# CFA_T.net
KiCad netlist of a schematic drawn in EAGLE
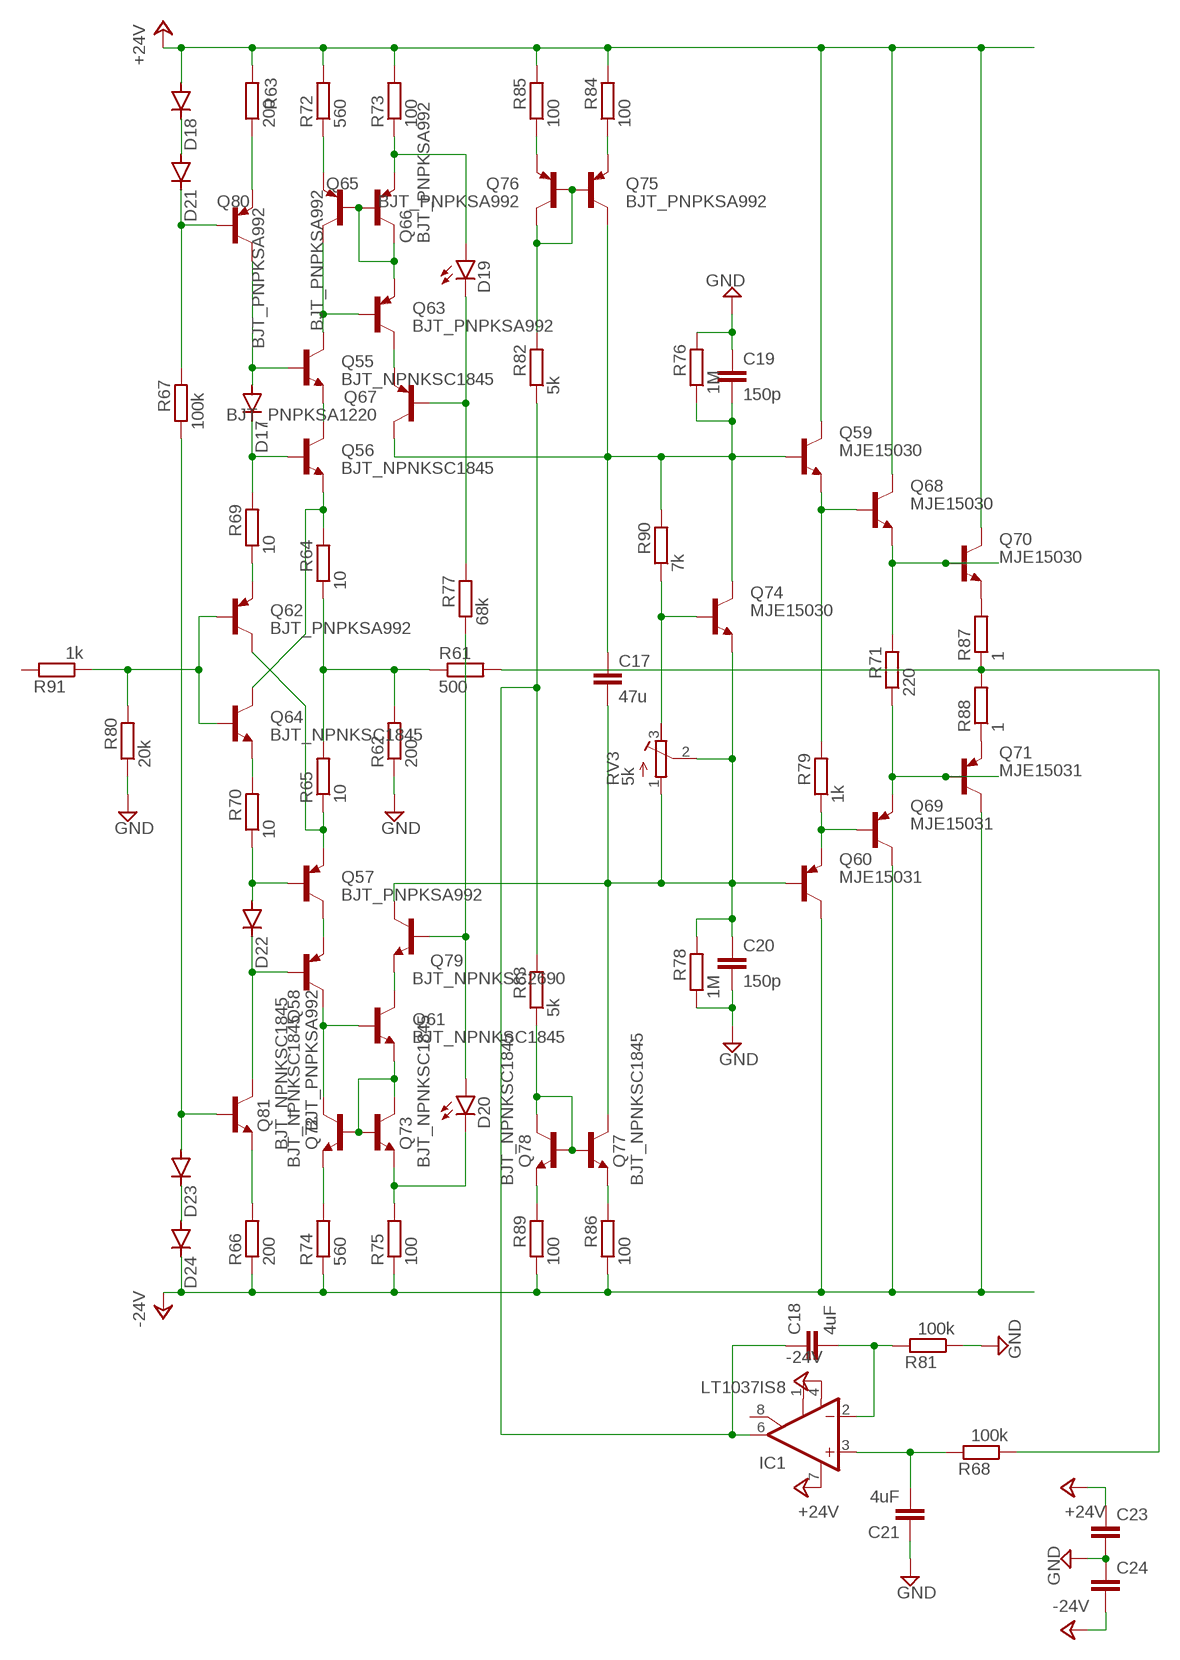
[diagram p0: schematic, sheet 1]

(export (version "E")
  (design (tool "Eeschema 10.0.6"))
  (components
    (comp (ref "C17")
      (value "47u")
      (footprint "eagle-import:C1210")
      (fields (field (name "SPICEPREFIX") "C"))
      (libsource (lib "eagle-import") (part "C-EUC1210"))
    )
    (comp (ref "C18")
      (value "4uF")
      (footprint "eagle-import:C1210")
      (fields (field (name "SPICEPREFIX") "C"))
      (libsource (lib "eagle-import") (part "C-EUC1210"))
    )
    (comp (ref "C19")
      (value "150p")
      (footprint "eagle-import:C0805")
      (fields (field (name "SPICEPREFIX") "C"))
      (libsource (lib "eagle-import") (part "C-EUC0805"))
    )
    (comp (ref "C20")
      (value "150p")
      (footprint "eagle-import:C0805")
      (fields (field (name "SPICEPREFIX") "C"))
      (libsource (lib "eagle-import") (part "C-EUC0805"))
    )
    (comp (ref "C21")
      (value "4uF")
      (footprint "eagle-import:C1210")
      (fields (field (name "SPICEPREFIX") "C"))
      (libsource (lib "eagle-import") (part "C-EUC1210"))
    )
    (comp (ref "C23")
      (value "C-EUC0603K")
      (footprint "eagle-import:C0603K")
      (libsource (lib "eagle-import") (part "C-EUC0603K"))
    )
    (comp (ref "C24")
      (value "C-EUC0603K")
      (footprint "eagle-import:C0603K")
      (libsource (lib "eagle-import") (part "C-EUC0603K"))
    )
    (comp (ref "D17")
      (value "DIODE-SOD80C")
      (footprint "eagle-import:SOD80C")
      (fields (field (name "SPICEPREFIX") "D"))
      (libsource (lib "eagle-import") (part "DIODE-SOD80C"))
    )
    (comp (ref "D18")
      (value "DIODE-SOD80C")
      (footprint "eagle-import:SOD80C")
      (fields (field (name "SPICEPREFIX") "D"))
      (libsource (lib "eagle-import") (part "DIODE-SOD80C"))
    )
    (comp (ref "D19")
      (value "LEDCHIPLED_1206")
      (footprint "eagle-import:CHIPLED_1206")
      (fields (field (name "SPICEPREFIX") "D"))
      (libsource (lib "eagle-import") (part "LEDCHIPLED_1206"))
    )
    (comp (ref "D20")
      (value "LEDCHIPLED_1206")
      (footprint "eagle-import:CHIPLED_1206")
      (fields (field (name "SPICEPREFIX") "D"))
      (libsource (lib "eagle-import") (part "LEDCHIPLED_1206"))
    )
    (comp (ref "D21")
      (value "DIODE-SOD80C")
      (footprint "eagle-import:SOD80C")
      (fields (field (name "SPICEPREFIX") "D"))
      (libsource (lib "eagle-import") (part "DIODE-SOD80C"))
    )
    (comp (ref "D22")
      (value "DIODE-SOD80C")
      (footprint "eagle-import:SOD80C")
      (fields (field (name "SPICEPREFIX") "D"))
      (libsource (lib "eagle-import") (part "DIODE-SOD80C"))
    )
    (comp (ref "D23")
      (value "DIODE-SOD80C")
      (footprint "eagle-import:SOD80C")
      (fields (field (name "SPICEPREFIX") "D"))
      (libsource (lib "eagle-import") (part "DIODE-SOD80C"))
    )
    (comp (ref "D24")
      (value "DIODE-SOD80C")
      (footprint "eagle-import:SOD80C")
      (fields (field (name "SPICEPREFIX") "D"))
      (libsource (lib "eagle-import") (part "DIODE-SOD80C"))
    )
    (comp (ref "IC1")
      (value "LT1037IS8")
      (footprint "eagle-import:SOIC8")
      (libsource (lib "eagle-import") (part "LT10S837I"))
    )
    (comp (ref "Q55")
      (value "BJT_NPNKSC1845")
      (footprint "eagle-import:TRANSISTOR_TO92-ECB")
      (fields (field (name "SPICEPREFIX") "Q"))
      (libsource (lib "eagle-import") (part "BJT_NPNKSC1845"))
    )
    (comp (ref "Q56")
      (value "BJT_NPNKSC1845")
      (footprint "eagle-import:TRANSISTOR_TO92-ECB")
      (fields (field (name "SPICEPREFIX") "Q"))
      (libsource (lib "eagle-import") (part "BJT_NPNKSC1845"))
    )
    (comp (ref "Q57")
      (value "BJT_PNPKSA992")
      (footprint "eagle-import:TRANSISTOR_TO92-ECB")
      (fields (field (name "SPICEPREFIX") "Q"))
      (libsource (lib "eagle-import") (part "BJT_PNPKSA992"))
    )
    (comp (ref "Q58")
      (value "BJT_PNPKSA992")
      (footprint "eagle-import:TRANSISTOR_TO92-ECB")
      (fields (field (name "SPICEPREFIX") "Q"))
      (libsource (lib "eagle-import") (part "BJT_PNPKSA992"))
    )
    (comp (ref "Q59")
      (value "MJE15030")
      (footprint "eagle-import:TRANSISTOR_TO92-ECB")
      (fields (field (name "SPICEPREFIX") "Q"))
      (libsource (lib "eagle-import") (part "BJT_NPNKSC1845"))
    )
    (comp (ref "Q60")
      (value "MJE15031")
      (footprint "eagle-import:TRANSISTOR_TO92-ECB")
      (fields (field (name "SPICEPREFIX") "Q"))
      (libsource (lib "eagle-import") (part "BJT_PNPKSA992"))
    )
    (comp (ref "Q61")
      (value "BJT_NPNKSC1845")
      (footprint "eagle-import:TRANSISTOR_TO92-ECB")
      (fields (field (name "SPICEPREFIX") "Q"))
      (libsource (lib "eagle-import") (part "BJT_NPNKSC1845"))
    )
    (comp (ref "Q62")
      (value "BJT_PNPKSA992")
      (footprint "eagle-import:TRANSISTOR_TO92-ECB")
      (fields (field (name "SPICEPREFIX") "Q"))
      (libsource (lib "eagle-import") (part "BJT_PNPKSA992"))
    )
    (comp (ref "Q63")
      (value "BJT_PNPKSA992")
      (footprint "eagle-import:TRANSISTOR_TO92-ECB")
      (fields (field (name "SPICEPREFIX") "Q"))
      (libsource (lib "eagle-import") (part "BJT_PNPKSA992"))
    )
    (comp (ref "Q64")
      (value "BJT_NPNKSC1845")
      (footprint "eagle-import:TRANSISTOR_TO92-ECB")
      (fields (field (name "SPICEPREFIX") "Q"))
      (libsource (lib "eagle-import") (part "BJT_NPNKSC1845"))
    )
    (comp (ref "Q65")
      (value "BJT_PNPKSA992")
      (footprint "eagle-import:TRANSISTOR_TO92-ECB")
      (fields (field (name "SPICEPREFIX") "Q"))
      (libsource (lib "eagle-import") (part "BJT_PNPKSA992"))
    )
    (comp (ref "Q66")
      (value "BJT_PNPKSA992")
      (footprint "eagle-import:TRANSISTOR_TO92-ECB")
      (fields (field (name "SPICEPREFIX") "Q"))
      (libsource (lib "eagle-import") (part "BJT_PNPKSA992"))
    )
    (comp (ref "Q67")
      (value "BJT_PNPKSA1220")
      (footprint "eagle-import:TRANSISTOR_TO126V")
      (fields (field (name "SPICEPREFIX") "Q"))
      (libsource (lib "eagle-import") (part "BJT_PNPKSA1220"))
    )
    (comp (ref "Q68")
      (value "MJE15030")
      (footprint "eagle-import:TRANSISTOR_TO92-ECB")
      (fields (field (name "SPICEPREFIX") "Q"))
      (libsource (lib "eagle-import") (part "BJT_NPNKSC1845"))
    )
    (comp (ref "Q69")
      (value "MJE15031")
      (footprint "eagle-import:TRANSISTOR_TO92-ECB")
      (fields (field (name "SPICEPREFIX") "Q"))
      (libsource (lib "eagle-import") (part "BJT_PNPKSA992"))
    )
    (comp (ref "Q70")
      (value "MJE15030")
      (footprint "eagle-import:TO264_TO-264")
      (fields (field (name "SPICEPREFIX") "Q"))
      (libsource (lib "eagle-import") (part "TO264_MJL4281"))
    )
    (comp (ref "Q71")
      (value "MJE15031")
      (footprint "eagle-import:TO264_TO-264")
      (fields (field (name "SPICEPREFIX") "Q"))
      (libsource (lib "eagle-import") (part "TO264_MJL4302"))
    )
    (comp (ref "Q72")
      (value "BJT_NPNKSC1845")
      (footprint "eagle-import:TRANSISTOR_TO92-ECB")
      (fields (field (name "SPICEPREFIX") "Q"))
      (libsource (lib "eagle-import") (part "BJT_NPNKSC1845"))
    )
    (comp (ref "Q73")
      (value "BJT_NPNKSC1845")
      (footprint "eagle-import:TRANSISTOR_TO92-ECB")
      (fields (field (name "SPICEPREFIX") "Q"))
      (libsource (lib "eagle-import") (part "BJT_NPNKSC1845"))
    )
    (comp (ref "Q74")
      (value "MJE15030")
      (footprint "eagle-import:TRANSISTOR_TO220KG")
      (fields (field (name "SPICEPREFIX") "Q"))
      (libsource (lib "eagle-import") (part "TRANSISTOR_MJE15030"))
    )
    (comp (ref "Q75")
      (value "BJT_PNPKSA992")
      (footprint "eagle-import:TRANSISTOR_TO92-ECB")
      (fields (field (name "SPICEPREFIX") "Q"))
      (libsource (lib "eagle-import") (part "BJT_PNPKSA992"))
    )
    (comp (ref "Q76")
      (value "BJT_PNPKSA992")
      (footprint "eagle-import:TRANSISTOR_TO92-ECB")
      (fields (field (name "SPICEPREFIX") "Q"))
      (libsource (lib "eagle-import") (part "BJT_PNPKSA992"))
    )
    (comp (ref "Q77")
      (value "BJT_NPNKSC1845")
      (footprint "eagle-import:TRANSISTOR_TO92-ECB")
      (fields (field (name "SPICEPREFIX") "Q"))
      (libsource (lib "eagle-import") (part "BJT_NPNKSC1845"))
    )
    (comp (ref "Q78")
      (value "BJT_NPNKSC1845")
      (footprint "eagle-import:TRANSISTOR_TO92-ECB")
      (fields (field (name "SPICEPREFIX") "Q"))
      (libsource (lib "eagle-import") (part "BJT_NPNKSC1845"))
    )
    (comp (ref "Q79")
      (value "BJT_NPNKSC2690")
      (footprint "eagle-import:TRANSISTOR_TO126V")
      (fields (field (name "SPICEPREFIX") "Q"))
      (libsource (lib "eagle-import") (part "BJT_NPNKSC2690"))
    )
    (comp (ref "Q80")
      (value "BJT_PNPKSA992")
      (footprint "eagle-import:TRANSISTOR_TO92-ECB")
      (fields (field (name "SPICEPREFIX") "Q"))
      (libsource (lib "eagle-import") (part "BJT_PNPKSA992"))
    )
    (comp (ref "Q81")
      (value "BJT_NPNKSC1845")
      (footprint "eagle-import:TRANSISTOR_TO92-ECB")
      (fields (field (name "SPICEPREFIX") "Q"))
      (libsource (lib "eagle-import") (part "BJT_NPNKSC1845"))
    )
    (comp (ref "R61")
      (value "500")
      (footprint "eagle-import:MINI_MELF-0204W")
      (fields (field (name "SPICEPREFIX") "R"))
      (libsource (lib "eagle-import") (part "R-EU_MELF0204W"))
    )
    (comp (ref "R62")
      (value "200")
      (footprint "eagle-import:MINI_MELF-0204W")
      (fields (field (name "SPICEPREFIX") "R"))
      (libsource (lib "eagle-import") (part "R-EU_MELF0204W"))
    )
    (comp (ref "R63")
      (value "200")
      (footprint "eagle-import:MINI_MELF-0204W")
      (fields (field (name "SPICEPREFIX") "R"))
      (libsource (lib "eagle-import") (part "R-EU_MELF0204W"))
    )
    (comp (ref "R64")
      (value "10")
      (footprint "eagle-import:MINI_MELF-0204W")
      (fields (field (name "SPICEPREFIX") "R"))
      (libsource (lib "eagle-import") (part "R-EU_MELF0204W"))
    )
    (comp (ref "R65")
      (value "10")
      (footprint "eagle-import:MINI_MELF-0204W")
      (fields (field (name "SPICEPREFIX") "R"))
      (libsource (lib "eagle-import") (part "R-EU_MELF0204W"))
    )
    (comp (ref "R66")
      (value "200")
      (footprint "eagle-import:MINI_MELF-0204W")
      (fields (field (name "SPICEPREFIX") "R"))
      (libsource (lib "eagle-import") (part "R-EU_MELF0204W"))
    )
    (comp (ref "R67")
      (value "100k")
      (footprint "eagle-import:MINI_MELF-0204W")
      (fields (field (name "SPICEPREFIX") "R"))
      (libsource (lib "eagle-import") (part "R-EU_MELF0204W"))
    )
    (comp (ref "R68")
      (value "100k")
      (footprint "eagle-import:MINI_MELF-0204W")
      (fields (field (name "SPICEPREFIX") "R"))
      (libsource (lib "eagle-import") (part "R-EU_MELF0204W"))
    )
    (comp (ref "R69")
      (value "10")
      (footprint "eagle-import:MINI_MELF-0204W")
      (fields (field (name "SPICEPREFIX") "R"))
      (libsource (lib "eagle-import") (part "R-EU_MELF0204W"))
    )
    (comp (ref "R70")
      (value "10")
      (footprint "eagle-import:MINI_MELF-0204W")
      (fields (field (name "SPICEPREFIX") "R"))
      (libsource (lib "eagle-import") (part "R-EU_MELF0204W"))
    )
    (comp (ref "R71")
      (value "220")
      (footprint "eagle-import:MINI_MELF-0204W")
      (fields (field (name "SPICEPREFIX") "R"))
      (libsource (lib "eagle-import") (part "R-EU_MELF0204W"))
    )
    (comp (ref "R72")
      (value "560")
      (footprint "eagle-import:MINI_MELF-0204W")
      (fields (field (name "SPICEPREFIX") "R"))
      (libsource (lib "eagle-import") (part "R-EU_MELF0204W"))
    )
    (comp (ref "R73")
      (value "100")
      (footprint "eagle-import:MINI_MELF-0204W")
      (fields (field (name "SPICEPREFIX") "R"))
      (libsource (lib "eagle-import") (part "R-EU_MELF0204W"))
    )
    (comp (ref "R74")
      (value "560")
      (footprint "eagle-import:MINI_MELF-0204W")
      (fields (field (name "SPICEPREFIX") "R"))
      (libsource (lib "eagle-import") (part "R-EU_MELF0204W"))
    )
    (comp (ref "R75")
      (value "100")
      (footprint "eagle-import:MINI_MELF-0204W")
      (fields (field (name "SPICEPREFIX") "R"))
      (libsource (lib "eagle-import") (part "R-EU_MELF0204W"))
    )
    (comp (ref "R76")
      (value "1M")
      (footprint "eagle-import:MINI_MELF-0204W")
      (fields (field (name "SPICEPREFIX") "R"))
      (libsource (lib "eagle-import") (part "R-EU_MELF0204W"))
    )
    (comp (ref "R77")
      (value "68k")
      (footprint "eagle-import:MINI_MELF-0204W")
      (fields (field (name "SPICEPREFIX") "R"))
      (libsource (lib "eagle-import") (part "R-EU_MELF0204W"))
    )
    (comp (ref "R78")
      (value "1M")
      (footprint "eagle-import:MINI_MELF-0204W")
      (fields (field (name "SPICEPREFIX") "R"))
      (libsource (lib "eagle-import") (part "R-EU_MELF0204W"))
    )
    (comp (ref "R79")
      (value "1k")
      (footprint "eagle-import:MINI_MELF-0204W")
      (fields (field (name "SPICEPREFIX") "R"))
      (libsource (lib "eagle-import") (part "R-EU_MELF0204W"))
    )
    (comp (ref "R80")
      (value "20k")
      (footprint "eagle-import:MINI_MELF-0204W")
      (fields (field (name "SPICEPREFIX") "R"))
      (libsource (lib "eagle-import") (part "R-EU_MELF0204W"))
    )
    (comp (ref "R81")
      (value "100k")
      (footprint "eagle-import:MINI_MELF-0204W")
      (fields (field (name "SPICEPREFIX") "R"))
      (libsource (lib "eagle-import") (part "R-EU_MELF0204W"))
    )
    (comp (ref "R82")
      (value "5k")
      (footprint "eagle-import:MINI_MELF-0204W")
      (fields (field (name "SPICEPREFIX") "R"))
      (libsource (lib "eagle-import") (part "R-EU_MELF0204W"))
    )
    (comp (ref "R83")
      (value "5k")
      (footprint "eagle-import:MINI_MELF-0204W")
      (fields (field (name "SPICEPREFIX") "R"))
      (libsource (lib "eagle-import") (part "R-EU_MELF0204W"))
    )
    (comp (ref "R84")
      (value "100")
      (footprint "eagle-import:MINI_MELF-0204W")
      (fields (field (name "SPICEPREFIX") "R"))
      (libsource (lib "eagle-import") (part "R-EU_MELF0204W"))
    )
    (comp (ref "R85")
      (value "100")
      (footprint "eagle-import:MINI_MELF-0204W")
      (fields (field (name "SPICEPREFIX") "R"))
      (libsource (lib "eagle-import") (part "R-EU_MELF0204W"))
    )
    (comp (ref "R86")
      (value "100")
      (footprint "eagle-import:MINI_MELF-0204W")
      (fields (field (name "SPICEPREFIX") "R"))
      (libsource (lib "eagle-import") (part "R-EU_MELF0204W"))
    )
    (comp (ref "R87")
      (value "1")
      (footprint "eagle-import:R2512")
      (fields (field (name "SPICEPREFIX") "R"))
      (libsource (lib "eagle-import") (part "R-EU_R2512"))
    )
    (comp (ref "R88")
      (value "1")
      (footprint "eagle-import:R2512")
      (fields (field (name "SPICEPREFIX") "R"))
      (libsource (lib "eagle-import") (part "R-EU_R2512"))
    )
    (comp (ref "R89")
      (value "100")
      (footprint "eagle-import:MINI_MELF-0204W")
      (fields (field (name "SPICEPREFIX") "R"))
      (libsource (lib "eagle-import") (part "R-EU_MELF0204W"))
    )
    (comp (ref "R90")
      (value "7k")
      (footprint "eagle-import:MINI_MELF-0204W")
      (fields (field (name "SPICEPREFIX") "R"))
      (libsource (lib "eagle-import") (part "R-EU_MELF0204W"))
    )
    (comp (ref "R91")
      (value "1k")
      (footprint "eagle-import:MINI_MELF-0204W")
      (fields (field (name "SPICEPREFIX") "R"))
      (libsource (lib "eagle-import") (part "R-EU_MELF0204W"))
    )
    (comp (ref "RV3")
      (value "5k")
      (footprint "eagle-import:RTRIM3296W")
      (fields (field (name "SPICEPREFIX") "Z"))
      (libsource (lib "eagle-import") (part "R-TRIMM3296W"))
    )
  )
  (nets
    (net (code "1") (name "+24V") (class "Default")
      (node (ref "C23") (pin "1") (pinfunction "1_1") (pintype "passive"))
      (node (ref "D18") (pin "A") (pinfunction "A_A") (pintype "passive"))
      (node (ref "IC1") (pin "7") (pinfunction "V+_7") (pintype "power_in"))
      (node (ref "Q59") (pin "C") (pinfunction "C_C") (pintype "passive"))
      (node (ref "Q68") (pin "C") (pinfunction "C_C") (pintype "passive"))
      (node (ref "Q70") (pin "C") (pinfunction "C_C") (pintype "passive"))
      (node (ref "R63") (pin "2") (pinfunction "2_2") (pintype "passive"))
      (node (ref "R72") (pin "2") (pinfunction "2_2") (pintype "passive"))
      (node (ref "R73") (pin "2") (pinfunction "2_2") (pintype "passive"))
      (node (ref "R84") (pin "2") (pinfunction "2_2") (pintype "passive"))
      (node (ref "R85") (pin "2") (pinfunction "2_2") (pintype "passive"))
    )
    (net (code "2") (name "-24V") (class "Default")
      (node (ref "C24") (pin "2") (pinfunction "2_2") (pintype "passive"))
      (node (ref "D24") (pin "C") (pinfunction "C_C") (pintype "passive"))
      (node (ref "IC1") (pin "4") (pinfunction "V-_4") (pintype "power_in"))
      (node (ref "Q60") (pin "C") (pinfunction "C_C") (pintype "passive"))
      (node (ref "Q69") (pin "C") (pinfunction "C_C") (pintype "passive"))
      (node (ref "Q71") (pin "C") (pinfunction "C_C") (pintype "passive"))
      (node (ref "R66") (pin "1") (pinfunction "1_1") (pintype "passive"))
      (node (ref "R74") (pin "1") (pinfunction "1_1") (pintype "passive"))
      (node (ref "R75") (pin "1") (pinfunction "1_1") (pintype "passive"))
      (node (ref "R86") (pin "1") (pinfunction "1_1") (pintype "passive"))
      (node (ref "R89") (pin "1") (pinfunction "1_1") (pintype "passive"))
    )
    (net (code "3") (name "GND") (class "Default")
      (node (ref "C19") (pin "1") (pinfunction "1_1") (pintype "passive"))
      (node (ref "C20") (pin "2") (pinfunction "2_2") (pintype "passive"))
      (node (ref "C21") (pin "1") (pinfunction "1_1") (pintype "passive"))
      (node (ref "C23") (pin "2") (pinfunction "2_2") (pintype "passive"))
      (node (ref "C24") (pin "1") (pinfunction "1_1") (pintype "passive"))
      (node (ref "R62") (pin "1") (pinfunction "1_1") (pintype "passive"))
      (node (ref "R76") (pin "2") (pinfunction "2_2") (pintype "passive"))
      (node (ref "R78") (pin "1") (pinfunction "1_1") (pintype "passive"))
      (node (ref "R80") (pin "1") (pinfunction "1_1") (pintype "passive"))
      (node (ref "R81") (pin "1") (pinfunction "1_1") (pintype "passive"))
    )
    (net (code "4") (name "Net-(D17-PadA)") (class "Default")
      (node (ref "D17") (pin "A") (pinfunction "A_A") (pintype "passive"))
      (node (ref "Q55") (pin "B") (pinfunction "B_B") (pintype "passive"))
      (node (ref "Q80") (pin "C") (pinfunction "C_C") (pintype "passive"))
    )
    (net (code "5") (name "Net-(D17-PadC)") (class "Default")
      (node (ref "D17") (pin "C") (pinfunction "C_C") (pintype "passive"))
      (node (ref "Q56") (pin "B") (pinfunction "B_B") (pintype "passive"))
      (node (ref "R69") (pin "2") (pinfunction "2_2") (pintype "passive"))
    )
    (net (code "6") (name "Net-(D18-PadC)") (class "Default")
      (node (ref "D18") (pin "C") (pinfunction "C_C") (pintype "passive"))
      (node (ref "D21") (pin "A") (pinfunction "A_A") (pintype "passive"))
    )
    (net (code "7") (name "Net-(D19-PadA)") (class "Default")
      (node (ref "D19") (pin "A") (pinfunction "A_A") (pintype "passive"))
      (node (ref "Q66") (pin "E") (pinfunction "E_E") (pintype "passive"))
      (node (ref "R73") (pin "1") (pinfunction "1_1") (pintype "passive"))
    )
    (net (code "8") (name "Net-(D19-PadC)") (class "Default")
      (node (ref "D19") (pin "C") (pinfunction "C_C") (pintype "passive"))
      (node (ref "Q67") (pin "B") (pinfunction "B_B") (pintype "passive"))
      (node (ref "R77") (pin "2") (pinfunction "2_2") (pintype "passive"))
    )
    (net (code "9") (name "Net-(D20-PadA)") (class "Default")
      (node (ref "D20") (pin "A") (pinfunction "A_A") (pintype "passive"))
      (node (ref "Q79") (pin "B") (pinfunction "B_B") (pintype "passive"))
      (node (ref "R77") (pin "1") (pinfunction "1_1") (pintype "passive"))
    )
    (net (code "10") (name "Net-(D20-PadC)") (class "Default")
      (node (ref "D20") (pin "C") (pinfunction "C_C") (pintype "passive"))
      (node (ref "Q73") (pin "E") (pinfunction "E_E") (pintype "passive"))
      (node (ref "R75") (pin "2") (pinfunction "2_2") (pintype "passive"))
    )
    (net (code "11") (name "Net-(D21-PadC)") (class "Default")
      (node (ref "D21") (pin "C") (pinfunction "C_C") (pintype "passive"))
      (node (ref "Q80") (pin "B") (pinfunction "B_B") (pintype "passive"))
      (node (ref "R67") (pin "2") (pinfunction "2_2") (pintype "passive"))
    )
    (net (code "12") (name "Net-(D22-PadA)") (class "Default")
      (node (ref "D22") (pin "A") (pinfunction "A_A") (pintype "passive"))
      (node (ref "Q57") (pin "B") (pinfunction "B_B") (pintype "passive"))
      (node (ref "R70") (pin "1") (pinfunction "1_1") (pintype "passive"))
    )
    (net (code "13") (name "Net-(D22-PadC)") (class "Default")
      (node (ref "D22") (pin "C") (pinfunction "C_C") (pintype "passive"))
      (node (ref "Q58") (pin "B") (pinfunction "B_B") (pintype "passive"))
      (node (ref "Q81") (pin "C") (pinfunction "C_C") (pintype "passive"))
    )
    (net (code "14") (name "Net-(D23-PadA)") (class "Default")
      (node (ref "D23") (pin "A") (pinfunction "A_A") (pintype "passive"))
      (node (ref "Q81") (pin "B") (pinfunction "B_B") (pintype "passive"))
      (node (ref "R67") (pin "1") (pinfunction "1_1") (pintype "passive"))
    )
    (net (code "15") (name "Net-(D23-PadC)") (class "Default")
      (node (ref "D23") (pin "C") (pinfunction "C_C") (pintype "passive"))
      (node (ref "D24") (pin "A") (pinfunction "A_A") (pintype "passive"))
    )
    (net (code "16") (name "Net-(IC1-+IN)") (class "Default")
      (node (ref "C21") (pin "2") (pinfunction "2_2") (pintype "passive"))
      (node (ref "IC1") (pin "3") (pinfunction "+IN_3") (pintype "input"))
      (node (ref "R68") (pin "2") (pinfunction "2_2") (pintype "passive"))
    )
    (net (code "17") (name "Net-(IC1--IN)") (class "Default")
      (node (ref "C18") (pin "2") (pinfunction "2_2") (pintype "passive"))
      (node (ref "IC1") (pin "2") (pinfunction "-IN_2") (pintype "input"))
      (node (ref "R81") (pin "2") (pinfunction "2_2") (pintype "passive"))
    )
    (net (code "18") (name "Net-(IC1-OUT)") (class "Default")
      (node (ref "C18") (pin "1") (pinfunction "1_1") (pintype "passive"))
      (node (ref "IC1") (pin "6") (pinfunction "OUT_6") (pintype "output"))
      (node (ref "R82") (pin "1") (pinfunction "1_1") (pintype "passive"))
      (node (ref "R83") (pin "2") (pinfunction "2_2") (pintype "passive"))
    )
    (net (code "19") (name "Net-(Q55-PadC)") (class "Default")
      (node (ref "Q55") (pin "C") (pinfunction "C_C") (pintype "passive"))
      (node (ref "Q63") (pin "B") (pinfunction "B_B") (pintype "passive"))
      (node (ref "Q65") (pin "C") (pinfunction "C_C") (pintype "passive"))
    )
    (net (code "20") (name "Net-(Q55-PadE)") (class "Default")
      (node (ref "Q55") (pin "E") (pinfunction "E_E") (pintype "passive"))
      (node (ref "Q56") (pin "C") (pinfunction "C_C") (pintype "passive"))
    )
    (net (code "21") (name "Net-(Q56-PadE)") (class "Default")
      (node (ref "Q56") (pin "E") (pinfunction "E_E") (pintype "passive"))
      (node (ref "Q64") (pin "C") (pinfunction "C_C") (pintype "passive"))
      (node (ref "R64") (pin "2") (pinfunction "2_2") (pintype "passive"))
    )
    (net (code "22") (name "Net-(Q57-PadC)") (class "Default")
      (node (ref "Q57") (pin "C") (pinfunction "C_C") (pintype "passive"))
      (node (ref "Q58") (pin "E") (pinfunction "E_E") (pintype "passive"))
    )
    (net (code "23") (name "Net-(Q57-PadE)") (class "Default")
      (node (ref "Q57") (pin "E") (pinfunction "E_E") (pintype "passive"))
      (node (ref "Q62") (pin "C") (pinfunction "C_C") (pintype "passive"))
      (node (ref "R65") (pin "1") (pinfunction "1_1") (pintype "passive"))
    )
    (net (code "24") (name "Net-(Q58-PadC)") (class "Default")
      (node (ref "Q58") (pin "C") (pinfunction "C_C") (pintype "passive"))
      (node (ref "Q61") (pin "B") (pinfunction "B_B") (pintype "passive"))
      (node (ref "Q72") (pin "C") (pinfunction "C_C") (pintype "passive"))
    )
    (net (code "25") (name "Net-(Q59-PadE)") (class "Default")
      (node (ref "Q59") (pin "E") (pinfunction "E_E") (pintype "passive"))
      (node (ref "Q68") (pin "B") (pinfunction "B_B") (pintype "passive"))
      (node (ref "R79") (pin "2") (pinfunction "2_2") (pintype "passive"))
    )
    (net (code "26") (name "Net-(Q60-PadE)") (class "Default")
      (node (ref "Q60") (pin "E") (pinfunction "E_E") (pintype "passive"))
      (node (ref "Q69") (pin "B") (pinfunction "B_B") (pintype "passive"))
      (node (ref "R79") (pin "1") (pinfunction "1_1") (pintype "passive"))
    )
    (net (code "27") (name "Net-(Q61-PadC)") (class "Default")
      (node (ref "Q61") (pin "C") (pinfunction "C_C") (pintype "passive"))
      (node (ref "Q79") (pin "E") (pinfunction "E_E") (pintype "passive"))
    )
    (net (code "28") (name "Net-(Q61-PadE)") (class "Default")
      (node (ref "Q61") (pin "E") (pinfunction "E_E") (pintype "passive"))
      (node (ref "Q72") (pin "B") (pinfunction "B_B") (pintype "passive"))
      (node (ref "Q73") (pin "B") (pinfunction "B_B") (pintype "passive"))
      (node (ref "Q73") (pin "C") (pinfunction "C_C") (pintype "passive"))
    )
    (net (code "29") (name "Net-(Q62-PadB)") (class "Default")
      (node (ref "Q62") (pin "B") (pinfunction "B_B") (pintype "passive"))
      (node (ref "Q64") (pin "B") (pinfunction "B_B") (pintype "passive"))
      (node (ref "R80") (pin "2") (pinfunction "2_2") (pintype "passive"))
      (node (ref "R91") (pin "1") (pinfunction "1_1") (pintype "passive"))
    )
    (net (code "30") (name "Net-(Q62-PadE)") (class "Default")
      (node (ref "Q62") (pin "E") (pinfunction "E_E") (pintype "passive"))
      (node (ref "R69") (pin "1") (pinfunction "1_1") (pintype "passive"))
    )
    (net (code "31") (name "Net-(Q63-PadC)") (class "Default")
      (node (ref "Q63") (pin "C") (pinfunction "C_C") (pintype "passive"))
      (node (ref "Q67") (pin "E") (pinfunction "E_E") (pintype "passive"))
    )
    (net (code "32") (name "Net-(Q63-PadE)") (class "Default")
      (node (ref "Q63") (pin "E") (pinfunction "E_E") (pintype "passive"))
      (node (ref "Q65") (pin "B") (pinfunction "B_B") (pintype "passive"))
      (node (ref "Q66") (pin "B") (pinfunction "B_B") (pintype "passive"))
      (node (ref "Q66") (pin "C") (pinfunction "C_C") (pintype "passive"))
    )
    (net (code "33") (name "Net-(Q64-PadE)") (class "Default")
      (node (ref "Q64") (pin "E") (pinfunction "E_E") (pintype "passive"))
      (node (ref "R70") (pin "2") (pinfunction "2_2") (pintype "passive"))
    )
    (net (code "34") (name "Net-(Q65-PadE)") (class "Default")
      (node (ref "Q65") (pin "E") (pinfunction "E_E") (pintype "passive"))
      (node (ref "R72") (pin "1") (pinfunction "1_1") (pintype "passive"))
    )
    (net (code "35") (name "Net-(Q68-PadE)") (class "Default")
      (node (ref "Q68") (pin "E") (pinfunction "E_E") (pintype "passive"))
      (node (ref "Q70") (pin "B") (pinfunction "B_B") (pintype "passive"))
      (node (ref "R71") (pin "2") (pinfunction "2_2") (pintype "passive"))
    )
    (net (code "36") (name "Net-(Q69-PadE)") (class "Default")
      (node (ref "Q69") (pin "E") (pinfunction "E_E") (pintype "passive"))
      (node (ref "Q71") (pin "B") (pinfunction "B_B") (pintype "passive"))
      (node (ref "R71") (pin "1") (pinfunction "1_1") (pintype "passive"))
    )
    (net (code "37") (name "Net-(Q70-PadE)") (class "Default")
      (node (ref "Q70") (pin "E") (pinfunction "E_E") (pintype "passive"))
      (node (ref "R87") (pin "2") (pinfunction "2_2") (pintype "passive"))
    )
    (net (code "38") (name "Net-(Q71-PadE)") (class "Default")
      (node (ref "Q71") (pin "E") (pinfunction "E_E") (pintype "passive"))
      (node (ref "R88") (pin "1") (pinfunction "1_1") (pintype "passive"))
    )
    (net (code "39") (name "Net-(Q72-PadE)") (class "Default")
      (node (ref "Q72") (pin "E") (pinfunction "E_E") (pintype "passive"))
      (node (ref "R74") (pin "2") (pinfunction "2_2") (pintype "passive"))
    )
    (net (code "40") (name "Net-(Q74-B)") (class "Default")
      (node (ref "Q74") (pin "1") (pinfunction "B_1") (pintype "passive"))
      (node (ref "R90") (pin "1") (pinfunction "1_1") (pintype "passive"))
      (node (ref "RV3") (pin "3") (pinfunction "E_3") (pintype "passive"))
    )
    (net (code "41") (name "Net-(Q74-C)") (class "Default")
      (node (ref "C17") (pin "1") (pinfunction "1_1") (pintype "passive"))
      (node (ref "C19") (pin "2") (pinfunction "2_2") (pintype "passive"))
      (node (ref "Q59") (pin "B") (pinfunction "B_B") (pintype "passive"))
      (node (ref "Q67") (pin "C") (pinfunction "C_C") (pintype "passive"))
      (node (ref "Q74") (pin "2") (pinfunction "C_2") (pintype "passive"))
      (node (ref "Q75") (pin "C") (pinfunction "C_C") (pintype "passive"))
      (node (ref "R76") (pin "1") (pinfunction "1_1") (pintype "passive"))
      (node (ref "R90") (pin "2") (pinfunction "2_2") (pintype "passive"))
    )
    (net (code "42") (name "Net-(Q74-E)") (class "Default")
      (node (ref "C17") (pin "2") (pinfunction "2_2") (pintype "passive"))
      (node (ref "C20") (pin "1") (pinfunction "1_1") (pintype "passive"))
      (node (ref "Q60") (pin "B") (pinfunction "B_B") (pintype "passive"))
      (node (ref "Q74") (pin "3") (pinfunction "E_3") (pintype "passive"))
      (node (ref "Q77") (pin "C") (pinfunction "C_C") (pintype "passive"))
      (node (ref "Q79") (pin "C") (pinfunction "C_C") (pintype "passive"))
      (node (ref "R78") (pin "2") (pinfunction "2_2") (pintype "passive"))
      (node (ref "RV3") (pin "1") (pinfunction "A_1") (pintype "passive"))
      (node (ref "RV3") (pin "2") (pinfunction "S_2") (pintype "passive"))
    )
    (net (code "43") (name "Net-(Q75-PadB)") (class "Default")
      (node (ref "Q75") (pin "B") (pinfunction "B_B") (pintype "passive"))
      (node (ref "Q76") (pin "B") (pinfunction "B_B") (pintype "passive"))
      (node (ref "Q76") (pin "C") (pinfunction "C_C") (pintype "passive"))
      (node (ref "R82") (pin "2") (pinfunction "2_2") (pintype "passive"))
    )
    (net (code "44") (name "Net-(Q75-PadE)") (class "Default")
      (node (ref "Q75") (pin "E") (pinfunction "E_E") (pintype "passive"))
      (node (ref "R84") (pin "1") (pinfunction "1_1") (pintype "passive"))
    )
    (net (code "45") (name "Net-(Q76-PadE)") (class "Default")
      (node (ref "Q76") (pin "E") (pinfunction "E_E") (pintype "passive"))
      (node (ref "R85") (pin "1") (pinfunction "1_1") (pintype "passive"))
    )
    (net (code "46") (name "Net-(Q77-PadB)") (class "Default")
      (node (ref "Q77") (pin "B") (pinfunction "B_B") (pintype "passive"))
      (node (ref "Q78") (pin "B") (pinfunction "B_B") (pintype "passive"))
      (node (ref "Q78") (pin "C") (pinfunction "C_C") (pintype "passive"))
      (node (ref "R83") (pin "1") (pinfunction "1_1") (pintype "passive"))
    )
    (net (code "47") (name "Net-(Q77-PadE)") (class "Default")
      (node (ref "Q77") (pin "E") (pinfunction "E_E") (pintype "passive"))
      (node (ref "R86") (pin "2") (pinfunction "2_2") (pintype "passive"))
    )
    (net (code "48") (name "Net-(Q78-PadE)") (class "Default")
      (node (ref "Q78") (pin "E") (pinfunction "E_E") (pintype "passive"))
      (node (ref "R89") (pin "2") (pinfunction "2_2") (pintype "passive"))
    )
    (net (code "49") (name "Net-(Q80-PadE)") (class "Default")
      (node (ref "Q80") (pin "E") (pinfunction "E_E") (pintype "passive"))
      (node (ref "R63") (pin "1") (pinfunction "1_1") (pintype "passive"))
    )
    (net (code "50") (name "Net-(Q81-PadE)") (class "Default")
      (node (ref "Q81") (pin "E") (pinfunction "E_E") (pintype "passive"))
      (node (ref "R66") (pin "2") (pinfunction "2_2") (pintype "passive"))
    )
    (net (code "51") (name "Net-(R61-Pad1)") (class "Default")
      (node (ref "R61") (pin "1") (pinfunction "1_1") (pintype "passive"))
      (node (ref "R62") (pin "2") (pinfunction "2_2") (pintype "passive"))
      (node (ref "R64") (pin "1") (pinfunction "1_1") (pintype "passive"))
      (node (ref "R65") (pin "2") (pinfunction "2_2") (pintype "passive"))
    )
    (net (code "52") (name "Net-(R61-Pad2)") (class "Default")
      (node (ref "R61") (pin "2") (pinfunction "2_2") (pintype "passive"))
      (node (ref "R68") (pin "1") (pinfunction "1_1") (pintype "passive"))
      (node (ref "R87") (pin "1") (pinfunction "1_1") (pintype "passive"))
      (node (ref "R88") (pin "2") (pinfunction "2_2") (pintype "passive"))
    )
    (net (code "53") (name "unconnected-(IC1-CMP1-Pad1)") (class "Default")
      (node (ref "IC1") (pin "1") (pinfunction "CMP1_1") (pintype "passive"))
    )
    (net (code "54") (name "unconnected-(IC1-CMP2-Pad8)") (class "Default")
      (node (ref "IC1") (pin "8") (pinfunction "CMP2_8") (pintype "passive"))
    )
    (net (code "55") (name "unconnected-(R91-Pad2)") (class "Default")
      (node (ref "R91") (pin "2") (pinfunction "2_2") (pintype "passive"))
    )
  )
)
